# MCU.net
KiCad netlist of a schematic drawn in Altium Designer
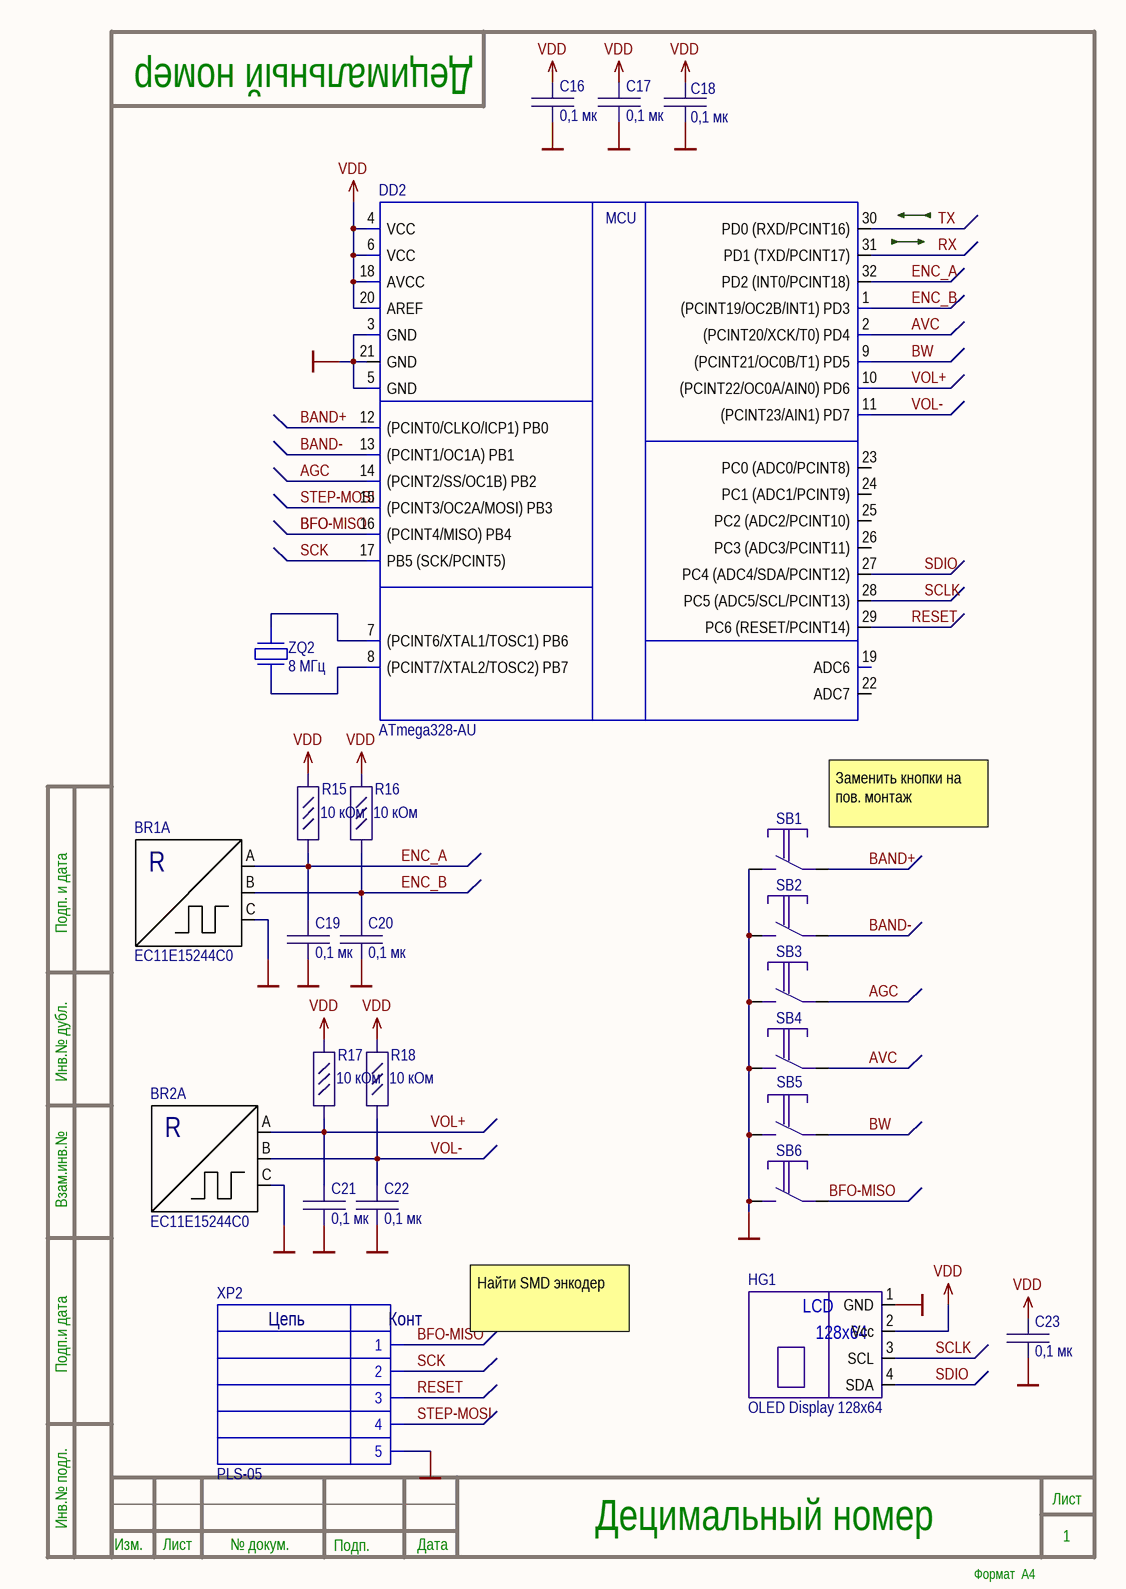
[diagram p0: MCU.SchDoc]

(export (version "E")
  (design (tool "Eeschema 10.0.6"))
  (components
    (comp (ref "BR1")
      (value "EC11E15244C0")
      (footprint "EC11")
      (libsource (lib "9.Commutation") (part "EC11E15244C0"))
    )
    (comp (ref "BR2")
      (value "EC11E15244C0")
      (footprint "EC11")
      (libsource (lib "9.Commutation") (part "EC11E15244C0"))
    )
    (comp (ref "C16")
      (value "0,1 мк")
      (footprint "C_0603")
      (description "CAP CER 0.1UF 100V X7R 0603")
      (fields
        (field (name "PART NUMBER") "GRM188R72A104MA35D")
        (field (name "MANUFACTURER") "Murata Electronics")
      )
      (libsource (lib "Database_Lib") (part "Capasitor"))
    )
    (comp (ref "C17")
      (value "0,1 мк")
      (footprint "C_0603")
      (description "CAP CER 0.1UF 100V X7R 0603")
      (fields
        (field (name "PART NUMBER") "GRM188R72A104MA35D")
        (field (name "MANUFACTURER") "Murata Electronics")
      )
      (libsource (lib "Database_Lib") (part "Capasitor"))
    )
    (comp (ref "C18")
      (value "0,1 мк")
      (footprint "C_0603")
      (description "CAP CER 0.1UF 100V X7R 0603")
      (fields
        (field (name "PART NUMBER") "GRM188R72A104MA35D")
        (field (name "MANUFACTURER") "Murata Electronics")
      )
      (libsource (lib "Database_Lib") (part "Capasitor"))
    )
    (comp (ref "C19")
      (value "0,1 мк")
      (footprint "C_0603")
      (description "CAP CER 0.1UF 100V X7R 0603")
      (fields
        (field (name "PART NUMBER") "GRM188R72A104MA35D")
        (field (name "MANUFACTURER") "Murata Electronics")
      )
      (libsource (lib "Database_Lib") (part "Capasitor"))
    )
    (comp (ref "C20")
      (value "0,1 мк")
      (footprint "C_0603")
      (description "CAP CER 0.1UF 100V X7R 0603")
      (fields
        (field (name "PART NUMBER") "GRM188R72A104MA35D")
        (field (name "MANUFACTURER") "Murata Electronics")
      )
      (libsource (lib "Database_Lib") (part "Capasitor"))
    )
    (comp (ref "C21")
      (value "0,1 мк")
      (footprint "C_0603")
      (description "CAP CER 0.1UF 100V X7R 0603")
      (fields
        (field (name "PART NUMBER") "GRM188R72A104MA35D")
        (field (name "MANUFACTURER") "Murata Electronics")
      )
      (libsource (lib "Database_Lib") (part "Capasitor"))
    )
    (comp (ref "C22")
      (value "0,1 мк")
      (footprint "C_0603")
      (description "CAP CER 0.1UF 100V X7R 0603")
      (fields
        (field (name "PART NUMBER") "GRM188R72A104MA35D")
        (field (name "MANUFACTURER") "Murata Electronics")
      )
      (libsource (lib "Database_Lib") (part "Capasitor"))
    )
    (comp (ref "C23")
      (value "0,1 мк")
      (footprint "C_0603")
      (description "CAP CER 0.1UF 100V X7R 0603")
      (fields
        (field (name "PART NUMBER") "GRM188R72A104MA35D")
        (field (name "MANUFACTURER") "Murata Electronics")
      )
      (libsource (lib "Database_Lib") (part "Capasitor"))
    )
    (comp (ref "DD2")
      (value "ATmega328-AU")
      (footprint "TQFP32")
      (libsource (lib "2. Chips") (part "ATmega328-AU"))
    )
    (comp (ref "HG1")
      (value "OLED Display 128x64")
      (footprint "OLED Display 128x64")
      (libsource (lib "8. Other") (part "OLED Display 128x64"))
    )
    (comp (ref "R15")
      (value "10 кОм")
      (footprint "R_0603")
      (description "RES SMD 10K OHM 1% 1/10W 0603")
      (fields (field (name "PART NUMBER") "CR0603-FX-1002ELF") (field (name "MANUFACTURER") "Bourns Inc."))
      (libsource (lib "Database_Lib") (part "Resistor"))
    )
    (comp (ref "R16")
      (value "10 кОм")
      (footprint "R_0603")
      (description "RES SMD 10K OHM 1% 1/10W 0603")
      (fields (field (name "PART NUMBER") "CR0603-FX-1002ELF") (field (name "MANUFACTURER") "Bourns Inc."))
      (libsource (lib "Database_Lib") (part "Resistor"))
    )
    (comp (ref "R17")
      (value "10 кОм")
      (footprint "R_0603")
      (description "RES SMD 10K OHM 1% 1/10W 0603")
      (fields (field (name "PART NUMBER") "CR0603-FX-1002ELF") (field (name "MANUFACTURER") "Bourns Inc."))
      (libsource (lib "Database_Lib") (part "Resistor"))
    )
    (comp (ref "R18")
      (value "10 кОм")
      (footprint "R_0603")
      (description "RES SMD 10K OHM 1% 1/10W 0603")
      (fields (field (name "PART NUMBER") "CR0603-FX-1002ELF") (field (name "MANUFACTURER") "Bourns Inc."))
      (libsource (lib "Database_Lib") (part "Resistor"))
    )
    (comp (ref "SB1")
      (value "KLS7-TS6601")
      (footprint "KLS7-TS6601")
      (libsource (lib "9.Commutation") (part "KLS7-TS6601"))
    )
    (comp (ref "SB2")
      (value "KLS7-TS6601")
      (footprint "KLS7-TS6601")
      (libsource (lib "9.Commutation") (part "KLS7-TS6601"))
    )
    (comp (ref "SB3")
      (value "KLS7-TS6601")
      (footprint "KLS7-TS6601")
      (libsource (lib "9.Commutation") (part "KLS7-TS6601"))
    )
    (comp (ref "SB4")
      (value "KLS7-TS6601")
      (footprint "KLS7-TS6601")
      (libsource (lib "9.Commutation") (part "KLS7-TS6601"))
    )
    (comp (ref "SB5")
      (value "KLS7-TS6601")
      (footprint "KLS7-TS6601")
      (libsource (lib "9.Commutation") (part "KLS7-TS6601"))
    )
    (comp (ref "SB6")
      (value "KLS7-TS6601")
      (footprint "KLS7-TS6601")
      (libsource (lib "9.Commutation") (part "KLS7-TS6601"))
    )
    (comp (ref "XP2") (value "PLS-05") (footprint "PLS-5") (libsource (lib "7. Connectors") (part "PLS-5")))
    (comp (ref "ZQ2")
      (value "8 МГц")
      (footprint "MJ CRYSTAL")
      (libsource (lib "8.Resonarors") (part "NX5032GA-8MHz"))
    )
  )
  (nets
    (net (code "1") (name "/AGC") (class "Default")
      (node (ref "DD2") (pin "14") (pinfunction "(PCINT2/SS/OC1B)_PB2_14") (pintype "passive"))
      (node (ref "SB3") (pin "2") (pinfunction "2_2") (pintype "passive"))
    )
    (net (code "2") (name "/AVC") (class "Default")
      (node (ref "DD2") (pin "2") (pinfunction "(PCINT20/XCK/T0)_PD4_2") (pintype "passive"))
      (node (ref "SB4") (pin "2") (pinfunction "2_2") (pintype "passive"))
    )
    (net (code "3") (name "/BAND+") (class "Default")
      (node (ref "DD2") (pin "12") (pinfunction "(PCINT0/CLKO/ICP1)_PB0_12") (pintype "passive"))
      (node (ref "SB1") (pin "2") (pinfunction "2_2") (pintype "passive"))
    )
    (net (code "4") (name "/BAND-") (class "Default")
      (node (ref "DD2") (pin "13") (pinfunction "(PCINT1/OC1A)_PB1_13") (pintype "passive"))
      (node (ref "SB2") (pin "2") (pinfunction "2_2") (pintype "passive"))
    )
    (net (code "5") (name "/BFO") (class "Default")
      (node (ref "DD2") (pin "16") (pinfunction "(PCINT4/MISO)_PB4_16") (pintype "passive"))
      (node (ref "SB6") (pin "2") (pinfunction "2_2") (pintype "passive"))
      (node (ref "XP2") (pin "1") (pinfunction "1_1") (pintype "passive"))
    )
    (net (code "6") (name "/BW") (class "Default")
      (node (ref "DD2") (pin "9") (pinfunction "(PCINT21/OC0B/T1)_PD5_9") (pintype "passive"))
      (node (ref "SB5") (pin "2") (pinfunction "2_2") (pintype "passive"))
    )
    (net (code "7") (name "/ENC_A") (class "Default")
      (node (ref "BR1") (pin "A") (pinfunction "A_A") (pintype "passive"))
      (node (ref "C19") (pin "1") (pinfunction "1_1") (pintype "passive"))
      (node (ref "DD2") (pin "32") (pinfunction "PD2_(INT0/PCINT18)_32") (pintype "passive"))
      (node (ref "R15") (pin "1") (pinfunction "1_1") (pintype "passive"))
    )
    (net (code "8") (name "/ENC_B") (class "Default")
      (node (ref "BR1") (pin "B") (pinfunction "B_B") (pintype "passive"))
      (node (ref "C20") (pin "1") (pinfunction "1_1") (pintype "passive"))
      (node (ref "DD2") (pin "1") (pinfunction "(PCINT19/OC2B/INT1)_PD3_1") (pintype "passive"))
      (node (ref "R16") (pin "1") (pinfunction "1_1") (pintype "passive"))
    )
    (net (code "9") (name "/RESET") (class "Default")
      (node (ref "DD2") (pin "29") (pinfunction "PC6_(RESET/PCINT14)_29") (pintype "passive"))
      (node (ref "XP2") (pin "3") (pinfunction "3_3") (pintype "passive"))
    )
    (net (code "10") (name "/RX") (class "Default")
      (node (ref "DD2") (pin "31") (pinfunction "PD1_(TXD/PCINT17)_31") (pintype "passive"))
    )
    (net (code "11") (name "/SCK") (class "Default")
      (node (ref "DD2") (pin "17") (pinfunction "PB5_(SCK/PCINT5)_17") (pintype "passive"))
      (node (ref "XP2") (pin "2") (pinfunction "2_2") (pintype "passive"))
    )
    (net (code "12") (name "/SCLK") (class "Default")
      (node (ref "DD2") (pin "28") (pinfunction "PC5_(ADC5/SCL/PCINT13)_28") (pintype "passive"))
      (node (ref "HG1") (pin "3") (pinfunction "SCL_3") (pintype "passive"))
    )
    (net (code "13") (name "/SDIO") (class "Default")
      (node (ref "DD2") (pin "27") (pinfunction "PC4_(ADC4/SDA/PCINT12)_27") (pintype "passive"))
      (node (ref "HG1") (pin "4") (pinfunction "SDA_4") (pintype "passive"))
    )
    (net (code "14") (name "/STEP-MOSI") (class "Default")
      (node (ref "DD2") (pin "15") (pinfunction "(PCINT3/OC2A/MOSI)_PB3_15") (pintype "passive"))
      (node (ref "XP2") (pin "4") (pinfunction "4_4") (pintype "passive"))
    )
    (net (code "15") (name "/TX") (class "Default")
      (node (ref "DD2") (pin "30") (pinfunction "PD0_(RXD/PCINT16)_30") (pintype "passive"))
    )
    (net (code "16") (name "/VOL+") (class "Default")
      (node (ref "BR2") (pin "A") (pinfunction "A_A") (pintype "passive"))
      (node (ref "C21") (pin "1") (pinfunction "1_1") (pintype "passive"))
      (node (ref "DD2") (pin "10") (pinfunction "(PCINT22/OC0A/AIN0)_PD6_10") (pintype "passive"))
      (node (ref "R17") (pin "1") (pinfunction "1_1") (pintype "passive"))
    )
    (net (code "17") (name "/VOL-") (class "Default")
      (node (ref "BR2") (pin "B") (pinfunction "B_B") (pintype "passive"))
      (node (ref "C22") (pin "1") (pinfunction "1_1") (pintype "passive"))
      (node (ref "DD2") (pin "11") (pinfunction "(PCINT23/AIN1)_PD7_11") (pintype "passive"))
      (node (ref "R18") (pin "1") (pinfunction "1_1") (pintype "passive"))
    )
    (net (code "18") (name "GND") (class "Default")
      (node (ref "BR1") (pin "C") (pinfunction "C_C") (pintype "passive"))
      (node (ref "BR2") (pin "C") (pinfunction "C_C") (pintype "passive"))
      (node (ref "C16") (pin "2") (pinfunction "2_2") (pintype "passive"))
      (node (ref "C17") (pin "2") (pinfunction "2_2") (pintype "passive"))
      (node (ref "C18") (pin "2") (pinfunction "2_2") (pintype "passive"))
      (node (ref "C19") (pin "2") (pinfunction "2_2") (pintype "passive"))
      (node (ref "C20") (pin "2") (pinfunction "2_2") (pintype "passive"))
      (node (ref "C21") (pin "2") (pinfunction "2_2") (pintype "passive"))
      (node (ref "C22") (pin "2") (pinfunction "2_2") (pintype "passive"))
      (node (ref "C23") (pin "2") (pinfunction "2_2") (pintype "passive"))
      (node (ref "DD2") (pin "21") (pinfunction "GND_21") (pintype "passive"))
      (node (ref "DD2") (pin "3") (pinfunction "GND_3") (pintype "passive"))
      (node (ref "DD2") (pin "5") (pinfunction "GND_5") (pintype "passive"))
      (node (ref "HG1") (pin "1") (pinfunction "GND_1") (pintype "passive"))
      (node (ref "SB1") (pin "1") (pinfunction "1_1") (pintype "passive"))
      (node (ref "SB2") (pin "1") (pinfunction "1_1") (pintype "passive"))
      (node (ref "SB3") (pin "1") (pinfunction "1_1") (pintype "passive"))
      (node (ref "SB4") (pin "1") (pinfunction "1_1") (pintype "passive"))
      (node (ref "SB5") (pin "1") (pinfunction "1_1") (pintype "passive"))
      (node (ref "SB6") (pin "1") (pinfunction "1_1") (pintype "passive"))
      (node (ref "XP2") (pin "5") (pinfunction "5_5") (pintype "passive"))
    )
    (net (code "19") (name "Net-(DD2-(PCINT6{slash}XTAL1{slash}TOSC1)_PB6)") (class "Default")
      (node (ref "DD2") (pin "7") (pinfunction "(PCINT6/XTAL1/TOSC1)_PB6_7") (pintype "passive"))
      (node (ref "ZQ2") (pin "3") (pinfunction "3_3") (pintype "passive"))
    )
    (net (code "20") (name "Net-(DD2-(PCINT7{slash}XTAL2{slash}TOSC2)_PB7)") (class "Default")
      (node (ref "DD2") (pin "8") (pinfunction "(PCINT7/XTAL2/TOSC2)_PB7_8") (pintype "passive"))
      (node (ref "ZQ2") (pin "1") (pinfunction "1_1") (pintype "passive"))
    )
    (net (code "21") (name "VDD") (class "Default")
      (node (ref "C16") (pin "1") (pinfunction "1_1") (pintype "passive"))
      (node (ref "C17") (pin "1") (pinfunction "1_1") (pintype "passive"))
      (node (ref "C18") (pin "1") (pinfunction "1_1") (pintype "passive"))
      (node (ref "C23") (pin "1") (pinfunction "1_1") (pintype "passive"))
      (node (ref "DD2") (pin "18") (pinfunction "AVCC_18") (pintype "passive"))
      (node (ref "DD2") (pin "20") (pinfunction "AREF_20") (pintype "passive"))
      (node (ref "DD2") (pin "4") (pinfunction "VCC_4") (pintype "passive"))
      (node (ref "DD2") (pin "6") (pinfunction "VCC_6") (pintype "passive"))
      (node (ref "HG1") (pin "2") (pinfunction "Vcc_2") (pintype "passive"))
      (node (ref "R15") (pin "2") (pinfunction "2_2") (pintype "passive"))
      (node (ref "R16") (pin "2") (pinfunction "2_2") (pintype "passive"))
      (node (ref "R17") (pin "2") (pinfunction "2_2") (pintype "passive"))
      (node (ref "R18") (pin "2") (pinfunction "2_2") (pintype "passive"))
    )
    (net (code "22") (name "unconnected-(DD2-ADC6-Pad19)") (class "Default")
      (node (ref "DD2") (pin "19") (pinfunction "ADC6_19") (pintype "passive"))
    )
    (net (code "23") (name "unconnected-(DD2-ADC7-Pad22)") (class "Default")
      (node (ref "DD2") (pin "22") (pinfunction "ADC7_22") (pintype "passive"))
    )
    (net (code "24") (name "unconnected-(DD2-PC0_(ADC0{slash}PCINT8)-Pad23)") (class "Default")
      (node (ref "DD2") (pin "23") (pinfunction "PC0_(ADC0/PCINT8)_23") (pintype "passive"))
    )
    (net (code "25") (name "unconnected-(DD2-PC1_(ADC1{slash}PCINT9)-Pad24)") (class "Default")
      (node (ref "DD2") (pin "24") (pinfunction "PC1_(ADC1/PCINT9)_24") (pintype "passive"))
    )
    (net (code "26") (name "unconnected-(DD2-PC2_(ADC2{slash}PCINT10)-Pad25)") (class "Default")
      (node (ref "DD2") (pin "25") (pinfunction "PC2_(ADC2/PCINT10)_25") (pintype "passive"))
    )
    (net (code "27") (name "unconnected-(DD2-PC3_(ADC3{slash}PCINT11)-Pad26)") (class "Default")
      (node (ref "DD2") (pin "26") (pinfunction "PC3_(ADC3/PCINT11)_26") (pintype "passive"))
    )
  )
)
